# Power_Supply.net
KiCad netlist of a schematic drawn in Altium Designer
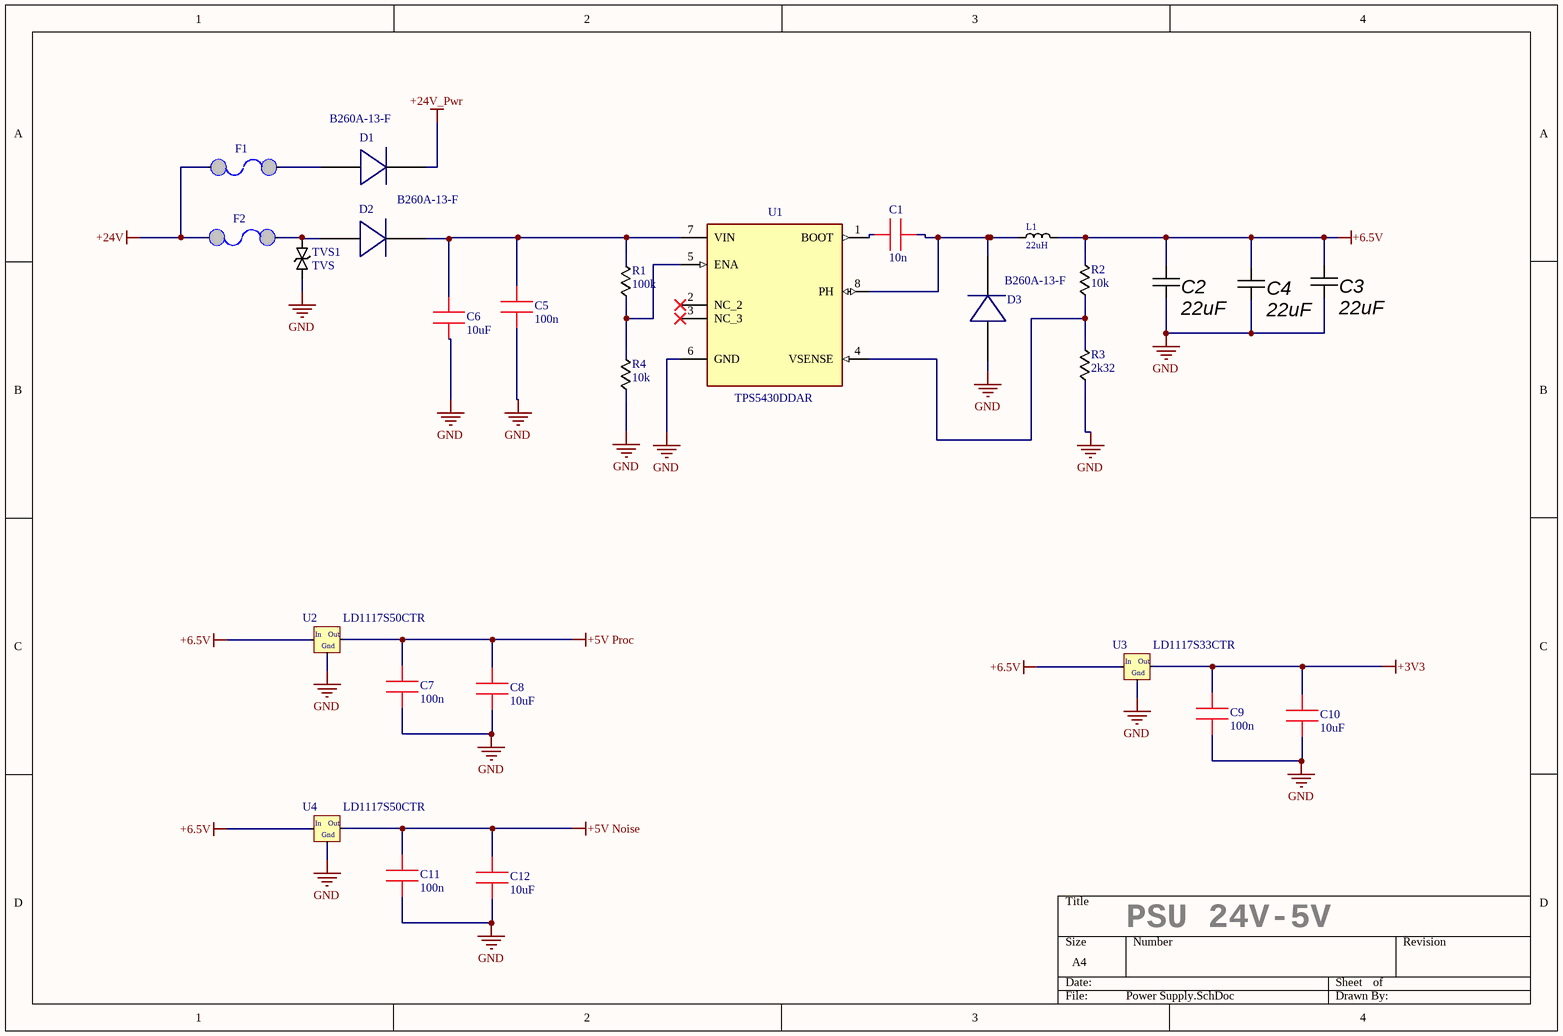
[diagram p0: Power Supply.SchDoc]

(export (version "E")
  (design (tool "Eeschema 10.0.6"))
  (components
    (comp (ref "C1")
      (value "10n")
      (footprint "0603")
      (description "CC0603JRX7R9BB103")
      (libsource (lib "kontr") (part "0603 CAP"))
    )
    (comp (ref "C2")
      (value "22uF")
      (footprint "0805")
      (description "CC0805MKX5R6BB226")
      (fields (field (name "TOLERANCE") "10%"))
      (libsource (lib "kontr") (part "Capacitor"))
    )
    (comp (ref "C3")
      (value "22uF")
      (footprint "0805")
      (description "CC0805MKX5R6BB226")
      (fields (field (name "TOLERANCE") "10%"))
      (libsource (lib "kontr") (part "Capacitor"))
    )
    (comp (ref "C4")
      (value "22uF")
      (footprint "PcbLib1:0805")
      (description "CC0805MKX5R6BB226")
      (fields (field (name "TOLERANCE") "10%"))
      (libsource (lib "kontr") (part "Capacitor"))
    )
    (comp (ref "C5")
      (value "100n")
      (footprint "0603")
      (description "CC0603KRX7R9BB104")
      (libsource (lib "kontr") (part "0603 CAP"))
    )
    (comp (ref "C6")
      (value "10uF")
      (footprint "1210")
      (description "GRM32ER71H106KA12L")
      (libsource (lib "kontr") (part "1206 Cap"))
    )
    (comp (ref "C7")
      (value "100n")
      (footprint "0603")
      (description "CC0603KRX7R9BB104")
      (libsource (lib "kontr") (part "0603 CAP"))
    )
    (comp (ref "C8")
      (value "10uF")
      (footprint "0603")
      (description "GRM188R61C106MA73D")
      (libsource (lib "kontr") (part "0603 CAP"))
    )
    (comp (ref "C9")
      (value "100n")
      (footprint "0603")
      (description "CC0603KRX7R9BB104")
      (libsource (lib "kontr") (part "0603 CAP"))
    )
    (comp (ref "C10")
      (value "10uF")
      (footprint "0603")
      (description "GRM188R61C106MA73D")
      (libsource (lib "kontr") (part "0603 CAP"))
    )
    (comp (ref "C11")
      (value "100n")
      (footprint "0603")
      (description "CC0603KRX7R9BB104")
      (libsource (lib "kontr") (part "0603 CAP"))
    )
    (comp (ref "C12")
      (value "10uF")
      (footprint "0603")
      (description "GRM188R61C106MA73D")
      (libsource (lib "kontr") (part "0603 CAP"))
    )
    (comp (ref "D1")
      (value "B260A-13-F")
      (footprint "DO-214Pol")
      (libsource (lib "kontr") (part "B260A-13-F"))
    )
    (comp (ref "D2")
      (value "B260A-13-F")
      (footprint "DO-214Pol")
      (libsource (lib "kontr") (part "B260A-13-F"))
    )
    (comp (ref "D3")
      (value "B260A-13-F")
      (footprint "DO-214Pol")
      (libsource (lib "kontr") (part "B260A-13-F"))
    )
    (comp (ref "F1")
      (value "Resettable FUSE")
      (footprint "1812")
      (description "MF-MSMF030-2")
      (libsource (lib "kontr") (part "Fuse PTS"))
    )
    (comp (ref "F2")
      (value "Resettable FUSE")
      (footprint "1812")
      (description "MF-MSMF030-2")
      (libsource (lib "kontr") (part "Fuse PTS"))
    )
    (comp (ref "L1")
      (value "22uH")
      (footprint "CDRH127")
      (description "CDRH127/LDNP-220MC")
      (libsource (lib "levin") (part "Inductor CDRH127"))
    )
    (comp (ref "R1")
      (value "100k")
      (footprint "0603")
      (description "RC0603FR-10100KL")
      (libsource (lib "kontr") (part "0603 RES"))
    )
    (comp (ref "R2")
      (value "10k")
      (footprint "0603")
      (description "RT0603FRE0710KL")
      (libsource (lib "kontr") (part "0603 RES"))
    )
    (comp (ref "R3")
      (value "2k32")
      (footprint "0603")
      (description "RC0603FR-072K32L")
      (libsource (lib "kontr") (part "0603 RES"))
    )
    (comp (ref "R4")
      (value "10k")
      (footprint "0603")
      (description "RT0603FRE0710KL")
      (libsource (lib "kontr") (part "0603 RES"))
    )
    (comp (ref "TVS1")
      (value "TVS")
      (footprint "DO-214AC")
      (description "SMAJ30CA")
      (libsource (lib "kontr") (part "TVS"))
    )
    (comp (ref "U1")
      (value "TPS5430DDAR")
      (footprint "levin:SOIC-8 + Thermal Pad")
      (libsource (lib "levin") (part "TPS5430DDAR"))
    )
    (comp (ref "U2") (value "LD1117S50CTR") (footprint "SOT223") (libsource (lib "kontr") (part "LDO")))
    (comp (ref "U3") (value "LD1117S33CTR") (footprint "SOT223") (libsource (lib "kontr") (part "LDO")))
    (comp (ref "U4") (value "LD1117S50CTR") (footprint "SOT223") (libsource (lib "kontr") (part "LDO")))
  )
  (nets
    (net (code "1") (name "+3V3") (class "Default")
      (node (ref "C10") (pin "1") (pinfunction "1_1") (pintype "passive"))
      (node (ref "C9") (pin "1") (pinfunction "1_1") (pintype "passive"))
      (node (ref "U3") (pin "2") (pinfunction "OUT_2") (pintype "passive"))
    )
    (net (code "2") (name "+5V Noise") (class "Default")
      (node (ref "C11") (pin "1") (pinfunction "1_1") (pintype "passive"))
      (node (ref "C12") (pin "1") (pinfunction "1_1") (pintype "passive"))
      (node (ref "U4") (pin "2") (pinfunction "OUT_2") (pintype "passive"))
    )
    (net (code "3") (name "+5V Proc") (class "Default")
      (node (ref "C7") (pin "1") (pinfunction "1_1") (pintype "passive"))
      (node (ref "C8") (pin "1") (pinfunction "1_1") (pintype "passive"))
      (node (ref "U2") (pin "2") (pinfunction "OUT_2") (pintype "passive"))
    )
    (net (code "4") (name "+6.5V") (class "Default")
      (node (ref "C2") (pin "2") (pinfunction "2_2") (pintype "passive"))
      (node (ref "C3") (pin "2") (pinfunction "2_2") (pintype "passive"))
      (node (ref "C4") (pin "2") (pinfunction "2_2") (pintype "passive"))
      (node (ref "L1") (pin "2") (pinfunction "2_2") (pintype "passive"))
      (node (ref "R2") (pin "2") (pintype "passive"))
      (node (ref "U2") (pin "3") (pinfunction "IN_3") (pintype "passive"))
      (node (ref "U3") (pin "3") (pinfunction "IN_3") (pintype "passive"))
      (node (ref "U4") (pin "3") (pinfunction "IN_3") (pintype "passive"))
    )
    (net (code "5") (name "+24V") (class "Default")
      (node (ref "F1") (pin "2") (pinfunction "2_2") (pintype "passive"))
      (node (ref "F2") (pin "2") (pinfunction "2_2") (pintype "passive"))
    )
    (net (code "6") (name "+24V_Pwr") (class "Default")
      (node (ref "D1") (pin "1") (pinfunction "1_1") (pintype "passive"))
    )
    (net (code "7") (name "GND") (class "Default")
      (node (ref "C10") (pin "2") (pinfunction "2_2") (pintype "passive"))
      (node (ref "C11") (pin "2") (pinfunction "2_2") (pintype "passive"))
      (node (ref "C12") (pin "2") (pinfunction "2_2") (pintype "passive"))
      (node (ref "C2") (pin "1") (pinfunction "1_1") (pintype "passive"))
      (node (ref "C3") (pin "1") (pinfunction "1_1") (pintype "passive"))
      (node (ref "C4") (pin "1") (pinfunction "1_1") (pintype "passive"))
      (node (ref "C5") (pin "1") (pinfunction "1_1") (pintype "passive"))
      (node (ref "C6") (pin "2") (pinfunction "2_2") (pintype "passive"))
      (node (ref "C7") (pin "2") (pinfunction "2_2") (pintype "passive"))
      (node (ref "C8") (pin "2") (pinfunction "2_2") (pintype "passive"))
      (node (ref "C9") (pin "2") (pinfunction "2_2") (pintype "passive"))
      (node (ref "D3") (pin "2") (pinfunction "1_2") (pintype "passive"))
      (node (ref "R3") (pin "1") (pintype "passive"))
      (node (ref "R4") (pin "1") (pintype "passive"))
      (node (ref "TVS1") (pin "2") (pinfunction "2_2") (pintype "passive"))
      (node (ref "U1") (pin "6") (pinfunction "GND_6") (pintype "power_in"))
      (node (ref "U2") (pin "1") (pinfunction "GND_1") (pintype "passive"))
      (node (ref "U3") (pin "1") (pinfunction "GND_1") (pintype "passive"))
      (node (ref "U4") (pin "1") (pinfunction "GND_1") (pintype "passive"))
    )
    (net (code "8") (name "Net-(D1-1-Pad2)") (class "Default")
      (node (ref "D1") (pin "2") (pinfunction "1_2") (pintype "passive"))
      (node (ref "F1") (pin "1") (pinfunction "1_1") (pintype "passive"))
    )
    (net (code "9") (name "Net-(D2-1-Pad2)") (class "Default")
      (node (ref "D2") (pin "2") (pinfunction "1_2") (pintype "passive"))
      (node (ref "F2") (pin "1") (pinfunction "1_1") (pintype "passive"))
      (node (ref "TVS1") (pin "1") (pinfunction "1_1") (pintype "passive"))
    )
    (net (code "10") (name "Net-(U1-BOOT)") (class "Default")
      (node (ref "C1") (pin "2") (pinfunction "2_2") (pintype "passive"))
      (node (ref "U1") (pin "1") (pinfunction "BOOT_1") (pintype "output"))
    )
    (net (code "11") (name "Net-(U1-ENA)") (class "Default")
      (node (ref "R1") (pin "1") (pintype "passive"))
      (node (ref "R4") (pin "2") (pintype "passive"))
      (node (ref "U1") (pin "5") (pinfunction "ENA_5") (pintype "input"))
    )
    (net (code "12") (name "Net-(U1-PH)") (class "Default")
      (node (ref "C1") (pin "1") (pinfunction "1_1") (pintype "passive"))
      (node (ref "D3") (pin "1") (pinfunction "1_1") (pintype "passive"))
      (node (ref "L1") (pin "1") (pinfunction "1_1") (pintype "passive"))
      (node (ref "U1") (pin "8") (pinfunction "PH_8") (pintype "bidirectional"))
    )
    (net (code "13") (name "Net-(U1-VIN)") (class "Default")
      (node (ref "C5") (pin "2") (pinfunction "2_2") (pintype "passive"))
      (node (ref "C6") (pin "1") (pinfunction "1_1") (pintype "passive"))
      (node (ref "D2") (pin "1") (pinfunction "1_1") (pintype "passive"))
      (node (ref "R1") (pin "2") (pintype "passive"))
      (node (ref "U1") (pin "7") (pinfunction "VIN_7") (pintype "power_in"))
    )
    (net (code "14") (name "Net-(U1-VSENSE)") (class "Default")
      (node (ref "R2") (pin "1") (pintype "passive"))
      (node (ref "R3") (pin "2") (pintype "passive"))
      (node (ref "U1") (pin "4") (pinfunction "VSENSE_4") (pintype "input"))
    )
    (net (code "15") (name "unconnected-(U1-NC_2-Pad2)") (class "Default")
      (node (ref "U1") (pin "2") (pinfunction "NC_2_2") (pintype "passive+no_connect"))
    )
    (net (code "16") (name "unconnected-(U1-NC_3-Pad3)") (class "Default")
      (node (ref "U1") (pin "3") (pinfunction "NC_3_3") (pintype "passive+no_connect"))
    )
  )
)
